# ziffy_board_v5.net
KiCad netlist of a schematic drawn in EAGLE
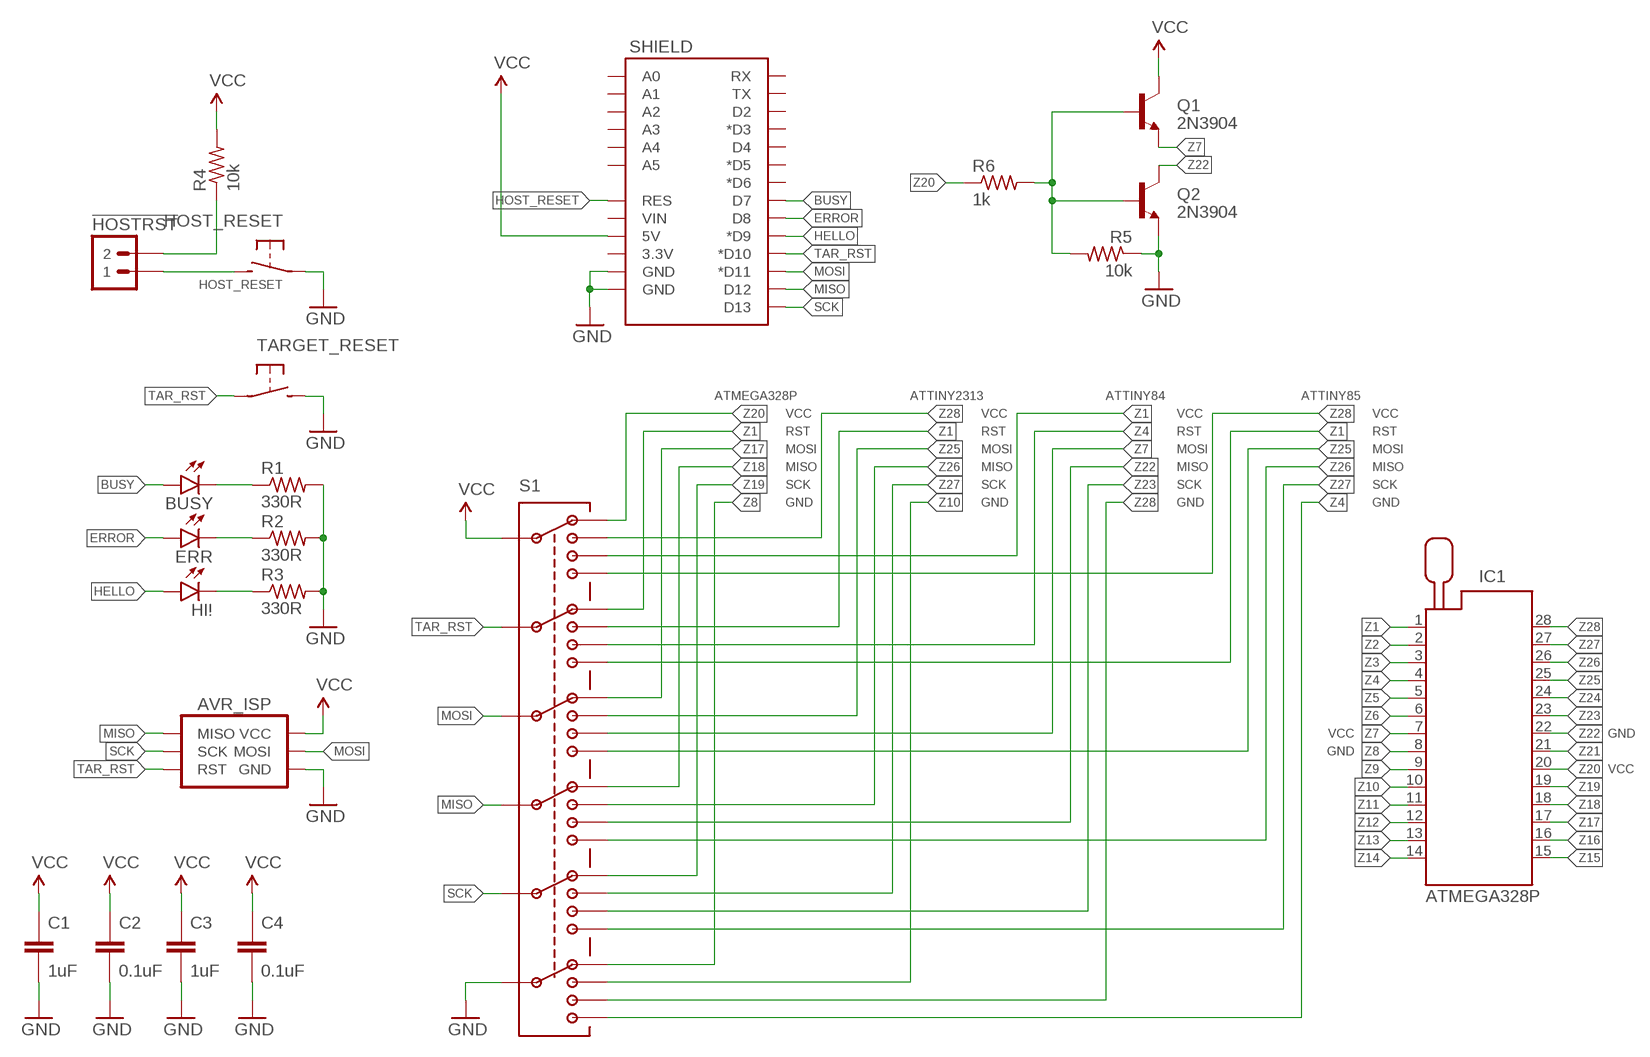
[diagram p0: schematic, sheet 1]

(export (version "E")
  (design (tool "Eeschema 10.0.6"))
  (components
    (comp (ref "!HOSTRST")
      (value "M02PTH")
      (footprint "eagle-import:1X02")
      (libsource (lib "eagle-import") (part "M02PTH"))
    )
    (comp (ref "AVR_ISP")
      (value "AVR_SPI_PRG_6PTH-SHROUD")
      (footprint "eagle-import:2X3-SHROUDED")
      (libsource (lib "eagle-import") (part "AVR_SPI_PRG_6PTH-SHROUD"))
    )
    (comp (ref "BUSY")
      (value "YELLOW")
      (footprint "eagle-import:LED3MM")
      (libsource (lib "eagle-import") (part "LED3MM"))
    )
    (comp (ref "C1")
      (value "1uF")
      (footprint "eagle-import:C025-024X044")
      (libsource (lib "eagle-import") (part "CAPACITOR-CERAMIC025-024X044"))
    )
    (comp (ref "C2")
      (value "0.1uF")
      (footprint "eagle-import:C025-024X044")
      (libsource (lib "eagle-import") (part "CAPACITOR-CERAMIC025-024X044"))
    )
    (comp (ref "C3")
      (value "1uF")
      (footprint "eagle-import:C025-024X044")
      (libsource (lib "eagle-import") (part "CAPACITOR-CERAMIC025-024X044"))
    )
    (comp (ref "C4")
      (value "0.1uF")
      (footprint "eagle-import:C025-024X044")
      (libsource (lib "eagle-import") (part "CAPACITOR-CERAMIC025-024X044"))
    )
    (comp (ref "ERR")
      (value "RED")
      (footprint "eagle-import:LED3MM")
      (libsource (lib "eagle-import") (part "LED3MM"))
    )
    (comp (ref "HI!")
      (value "GREEN")
      (footprint "eagle-import:LED3MM")
      (libsource (lib "eagle-import") (part "LED3MM"))
    )
    (comp (ref "HOST_RESET")
      (value "SPST-NO-TACT6MM-PTH-SMALL-PADS")
      (footprint "eagle-import:DTS-6-SMALL-PADS")
      (libsource (lib "eagle-import") (part "SPST-NO-TACT6MM-PTH-SMALL-PADS"))
    )
    (comp (ref "IC1")
      (value "ATMEGA328P")
      (footprint "eagle-import:ZIF28")
      (libsource (lib "eagle-import") (part "ZIF28"))
    )
    (comp (ref "Q1")
      (value "2N3904")
      (footprint "eagle-import:TO-92-AMMO")
      (libsource (lib "eagle-import") (part "TRANSISTOR_NPNTO-92-AMMO-EBC"))
    )
    (comp (ref "Q2")
      (value "2N3904")
      (footprint "eagle-import:TO-92-AMMO")
      (libsource (lib "eagle-import") (part "TRANSISTOR_NPNTO-92-AMMO-EBC"))
    )
    (comp (ref "R1")
      (value "330R")
      (footprint "eagle-import:RESISTOR-AXIAL-PTH-6.35MM")
      (libsource (lib "eagle-import") (part "RESISTORPTH-AXIAL-6.35MM"))
    )
    (comp (ref "R2")
      (value "330R")
      (footprint "eagle-import:RESISTOR-AXIAL-PTH-6.35MM")
      (libsource (lib "eagle-import") (part "RESISTORPTH-AXIAL-6.35MM"))
    )
    (comp (ref "R3")
      (value "330R")
      (footprint "eagle-import:RESISTOR-AXIAL-PTH-6.35MM")
      (libsource (lib "eagle-import") (part "RESISTORPTH-AXIAL-6.35MM"))
    )
    (comp (ref "R4")
      (value "10k")
      (footprint "eagle-import:RESISTOR-AXIAL-PTH-6.35MM")
      (libsource (lib "eagle-import") (part "RESISTORPTH-AXIAL-6.35MM"))
    )
    (comp (ref "R5")
      (value "10k")
      (footprint "eagle-import:RESISTOR-AXIAL-PTH-6.35MM")
      (libsource (lib "eagle-import") (part "RESISTORPTH-AXIAL-6.35MM"))
    )
    (comp (ref "R6")
      (value "1k")
      (footprint "eagle-import:RESISTOR-AXIAL-PTH-6.35MM")
      (libsource (lib "eagle-import") (part "RESISTORPTH-AXIAL-6.35MM"))
    )
    (comp (ref "S1")
      (value "SWITCH-6P4TASDFADSFSD")
      (footprint "eagle-import:SWITCH-6P4T-2MMPTH")
      (libsource (lib "eagle-import") (part "SWITCH-6P4TASDFADSFSD"))
    )
    (comp (ref "SHIELD")
      (value "ARDUINO_SHIELD_SMALLER")
      (footprint "eagle-import:ARDUINO_SHIELD_NOOUTLINE_INSIDE_SMALLER")
      (libsource (lib "eagle-import") (part "ARDUINO_SHIELD_SMALLER"))
    )
    (comp (ref "TARGET_RESET")
      (value "SPST-NO-TACT6MM-PTH-SMALL-PADS")
      (footprint "eagle-import:DTS-6-SMALL-PADS")
      (libsource (lib "eagle-import") (part "SPST-NO-TACT6MM-PTH-SMALL-PADS"))
    )
  )
  (nets
    (net (code "1") (name "BUSY") (class "Default")
      (node (ref "BUSY") (pin "A") (pinfunction "A_A") (pintype "passive"))
      (node (ref "SHIELD") (pin "D7") (pinfunction "D7_D7") (pintype "bidirectional"))
    )
    (net (code "2") (name "ERROR") (class "Default")
      (node (ref "ERR") (pin "A") (pinfunction "A_A") (pintype "passive"))
      (node (ref "SHIELD") (pin "D8") (pinfunction "D8_D8") (pintype "bidirectional"))
    )
    (net (code "3") (name "GND") (class "Default")
      (node (ref "AVR_ISP") (pin "6") (pinfunction "GND_6") (pintype "passive"))
      (node (ref "C1") (pin "2") (pinfunction "2_2") (pintype "passive"))
      (node (ref "C2") (pin "2") (pinfunction "2_2") (pintype "passive"))
      (node (ref "C3") (pin "2") (pinfunction "2_2") (pintype "passive"))
      (node (ref "C4") (pin "2") (pinfunction "2_2") (pintype "passive"))
      (node (ref "HOST_RESET") (pin "1") (pinfunction "1_1") (pintype "passive"))
      (node (ref "HOST_RESET") (pin "2") (pinfunction "1_2") (pintype "passive"))
      (node (ref "Q2") (pin "1") (pinfunction "E_1") (pintype "passive"))
      (node (ref "R1") (pin "P$2") (pinfunction "2_P$2") (pintype "passive"))
      (node (ref "R2") (pin "P$2") (pinfunction "2_P$2") (pintype "passive"))
      (node (ref "R3") (pin "P$2") (pinfunction "2_P$2") (pintype "passive"))
      (node (ref "R5") (pin "P$1") (pinfunction "1_P$1") (pintype "passive"))
      (node (ref "S1") (pin "P28") (pinfunction "28_P28") (pintype "bidirectional"))
      (node (ref "SHIELD") (pin "GND@0") (pinfunction "GND_GND@0") (pintype "bidirectional"))
      (node (ref "SHIELD") (pin "GND@1") (pinfunction "GND_GND@1") (pintype "bidirectional"))
      (node (ref "TARGET_RESET") (pin "3") (pinfunction "2_3") (pintype "passive"))
      (node (ref "TARGET_RESET") (pin "4") (pinfunction "2_4") (pintype "passive"))
    )
    (net (code "4") (name "HELLO") (class "Default")
      (node (ref "HI!") (pin "A") (pinfunction "A_A") (pintype "passive"))
      (node (ref "SHIELD") (pin "D9") (pinfunction "*D9_D9") (pintype "bidirectional"))
    )
    (net (code "5") (name "HOST_RESET") (class "Default")
      (node (ref "!HOSTRST") (pin "1") (pinfunction "1_1") (pintype "passive"))
      (node (ref "HOST_RESET") (pin "3") (pinfunction "2_3") (pintype "passive"))
      (node (ref "HOST_RESET") (pin "4") (pinfunction "2_4") (pintype "passive"))
      (node (ref "SHIELD") (pin "RES") (pinfunction "RES_RES") (pintype "bidirectional"))
    )
    (net (code "6") (name "MISO") (class "Default")
      (node (ref "AVR_ISP") (pin "1") (pinfunction "MISO_1") (pintype "passive"))
      (node (ref "S1") (pin "P18") (pinfunction "18_P18") (pintype "bidirectional"))
      (node (ref "SHIELD") (pin "D12") (pinfunction "D12_D12") (pintype "bidirectional"))
    )
    (net (code "7") (name "MOSI") (class "Default")
      (node (ref "AVR_ISP") (pin "4") (pinfunction "MOSI_4") (pintype "passive"))
      (node (ref "S1") (pin "P13") (pinfunction "13_P13") (pintype "bidirectional"))
      (node (ref "SHIELD") (pin "D11") (pinfunction "*D11_D11") (pintype "bidirectional"))
    )
    (net (code "8") (name "Net-(BUSY-C)") (class "Default")
      (node (ref "BUSY") (pin "K") (pinfunction "C_K") (pintype "passive"))
      (node (ref "R1") (pin "P$1") (pinfunction "1_P$1") (pintype "passive"))
    )
    (net (code "9") (name "Net-(ERR-C)") (class "Default")
      (node (ref "ERR") (pin "K") (pinfunction "C_K") (pintype "passive"))
      (node (ref "R2") (pin "P$1") (pinfunction "1_P$1") (pintype "passive"))
    )
    (net (code "10") (name "Net-(HI!-C)") (class "Default")
      (node (ref "HI!") (pin "K") (pinfunction "C_K") (pintype "passive"))
      (node (ref "R3") (pin "P$1") (pinfunction "1_P$1") (pintype "passive"))
    )
    (net (code "11") (name "Net-(Q1-B)") (class "Default")
      (node (ref "Q1") (pin "2") (pinfunction "B_2") (pintype "passive"))
      (node (ref "Q2") (pin "2") (pinfunction "B_2") (pintype "passive"))
      (node (ref "R5") (pin "P$2") (pinfunction "2_P$2") (pintype "passive"))
      (node (ref "R6") (pin "P$2") (pinfunction "2_P$2") (pintype "passive"))
    )
    (net (code "12") (name "Net-(R4-1)") (class "Default")
      (node (ref "!HOSTRST") (pin "2") (pinfunction "2_2") (pintype "passive"))
      (node (ref "R4") (pin "P$1") (pinfunction "1_P$1") (pintype "passive"))
    )
    (net (code "13") (name "SCK") (class "Default")
      (node (ref "AVR_ISP") (pin "3") (pinfunction "SCK_3") (pintype "passive"))
      (node (ref "S1") (pin "P23") (pinfunction "23_P23") (pintype "bidirectional"))
      (node (ref "SHIELD") (pin "D13") (pinfunction "D13_D13") (pintype "bidirectional"))
    )
    (net (code "14") (name "TAR_RST") (class "Default")
      (node (ref "AVR_ISP") (pin "5") (pinfunction "RST_5") (pintype "passive"))
      (node (ref "S1") (pin "P8") (pinfunction "8_P8") (pintype "bidirectional"))
      (node (ref "SHIELD") (pin "D10") (pinfunction "*D10_D10") (pintype "bidirectional"))
      (node (ref "TARGET_RESET") (pin "1") (pinfunction "1_1") (pintype "passive"))
      (node (ref "TARGET_RESET") (pin "2") (pinfunction "1_2") (pintype "passive"))
    )
    (net (code "15") (name "VCC") (class "Default")
      (node (ref "AVR_ISP") (pin "2") (pinfunction "VCC_2") (pintype "passive"))
      (node (ref "C1") (pin "1") (pinfunction "1_1") (pintype "passive"))
      (node (ref "C2") (pin "1") (pinfunction "1_1") (pintype "passive"))
      (node (ref "C3") (pin "1") (pinfunction "1_1") (pintype "passive"))
      (node (ref "C4") (pin "1") (pinfunction "1_1") (pintype "passive"))
      (node (ref "Q1") (pin "3") (pinfunction "C_3") (pintype "passive"))
      (node (ref "R4") (pin "P$2") (pinfunction "2_P$2") (pintype "passive"))
      (node (ref "S1") (pin "P3") (pinfunction "3_P3") (pintype "bidirectional"))
      (node (ref "SHIELD") (pin "5V") (pinfunction "5V_5V") (pintype "bidirectional"))
    )
    (net (code "16") (name "Z1") (class "Default")
      (node (ref "IC1") (pin "1") (pinfunction "1_1") (pintype "passive"))
      (node (ref "S1") (pin "P10") (pinfunction "10_P10") (pintype "bidirectional"))
      (node (ref "S1") (pin "P4") (pinfunction "4_P4") (pintype "bidirectional"))
      (node (ref "S1") (pin "P6") (pinfunction "6_P6") (pintype "bidirectional"))
      (node (ref "S1") (pin "P7") (pinfunction "7_P7") (pintype "bidirectional"))
    )
    (net (code "17") (name "Z2") (class "Default")
      (node (ref "IC1") (pin "2") (pinfunction "2_2") (pintype "passive"))
    )
    (net (code "18") (name "Z3") (class "Default")
      (node (ref "IC1") (pin "3") (pinfunction "3_3") (pintype "passive"))
    )
    (net (code "19") (name "Z4") (class "Default")
      (node (ref "IC1") (pin "4") (pinfunction "4_4") (pintype "passive"))
      (node (ref "S1") (pin "P30") (pinfunction "30_P30") (pintype "bidirectional"))
      (node (ref "S1") (pin "P9") (pinfunction "9_P9") (pintype "bidirectional"))
    )
    (net (code "20") (name "Z5") (class "Default")
      (node (ref "IC1") (pin "5") (pinfunction "5_5") (pintype "passive"))
    )
    (net (code "21") (name "Z6") (class "Default")
      (node (ref "IC1") (pin "6") (pinfunction "6_6") (pintype "passive"))
    )
    (net (code "22") (name "Z7") (class "Default")
      (node (ref "IC1") (pin "7") (pinfunction "7_7") (pintype "passive"))
      (node (ref "Q1") (pin "1") (pinfunction "E_1") (pintype "passive"))
      (node (ref "S1") (pin "P14") (pinfunction "14_P14") (pintype "bidirectional"))
    )
    (net (code "23") (name "Z8") (class "Default")
      (node (ref "IC1") (pin "8") (pinfunction "8_8") (pintype "passive"))
      (node (ref "S1") (pin "P26") (pinfunction "26_P26") (pintype "bidirectional"))
    )
    (net (code "24") (name "Z9") (class "Default")
      (node (ref "IC1") (pin "9") (pinfunction "9_9") (pintype "passive"))
    )
    (net (code "25") (name "Z10") (class "Default")
      (node (ref "IC1") (pin "10") (pinfunction "10_10") (pintype "passive"))
      (node (ref "S1") (pin "P27") (pinfunction "27_P27") (pintype "bidirectional"))
    )
    (net (code "26") (name "Z11") (class "Default")
      (node (ref "IC1") (pin "11") (pinfunction "11_11") (pintype "passive"))
    )
    (net (code "27") (name "Z12") (class "Default")
      (node (ref "IC1") (pin "12") (pinfunction "12_12") (pintype "passive"))
    )
    (net (code "28") (name "Z13") (class "Default")
      (node (ref "IC1") (pin "13") (pinfunction "13_13") (pintype "passive"))
    )
    (net (code "29") (name "Z14") (class "Default")
      (node (ref "IC1") (pin "14") (pinfunction "14_14") (pintype "passive"))
    )
    (net (code "30") (name "Z15") (class "Default")
      (node (ref "IC1") (pin "15") (pinfunction "15_15") (pintype "passive"))
    )
    (net (code "31") (name "Z16") (class "Default")
      (node (ref "IC1") (pin "16") (pinfunction "16_16") (pintype "passive"))
    )
    (net (code "32") (name "Z17") (class "Default")
      (node (ref "IC1") (pin "17") (pinfunction "17_17") (pintype "passive"))
      (node (ref "S1") (pin "P11") (pinfunction "11_P11") (pintype "bidirectional"))
    )
    (net (code "33") (name "Z18") (class "Default")
      (node (ref "IC1") (pin "18") (pinfunction "18_18") (pintype "passive"))
      (node (ref "S1") (pin "P16") (pinfunction "16_P16") (pintype "bidirectional"))
    )
    (net (code "34") (name "Z19") (class "Default")
      (node (ref "IC1") (pin "19") (pinfunction "19_19") (pintype "passive"))
      (node (ref "S1") (pin "P21") (pinfunction "21_P21") (pintype "bidirectional"))
    )
    (net (code "35") (name "Z20") (class "Default")
      (node (ref "IC1") (pin "20") (pinfunction "20_20") (pintype "passive"))
      (node (ref "R6") (pin "P$1") (pinfunction "1_P$1") (pintype "passive"))
      (node (ref "S1") (pin "P1") (pinfunction "1_P1") (pintype "bidirectional"))
    )
    (net (code "36") (name "Z21") (class "Default")
      (node (ref "IC1") (pin "21") (pinfunction "21_21") (pintype "passive"))
    )
    (net (code "37") (name "Z22") (class "Default")
      (node (ref "IC1") (pin "22") (pinfunction "22_22") (pintype "passive"))
      (node (ref "Q2") (pin "3") (pinfunction "C_3") (pintype "passive"))
      (node (ref "S1") (pin "P19") (pinfunction "19_P19") (pintype "bidirectional"))
    )
    (net (code "38") (name "Z23") (class "Default")
      (node (ref "IC1") (pin "23") (pinfunction "23_23") (pintype "passive"))
      (node (ref "S1") (pin "P24") (pinfunction "24_P24") (pintype "bidirectional"))
    )
    (net (code "39") (name "Z24") (class "Default")
      (node (ref "IC1") (pin "24") (pinfunction "24_24") (pintype "passive"))
    )
    (net (code "40") (name "Z25") (class "Default")
      (node (ref "IC1") (pin "25") (pinfunction "25_25") (pintype "passive"))
      (node (ref "S1") (pin "P12") (pinfunction "12_P12") (pintype "bidirectional"))
      (node (ref "S1") (pin "P15") (pinfunction "15_P15") (pintype "bidirectional"))
    )
    (net (code "41") (name "Z26") (class "Default")
      (node (ref "IC1") (pin "26") (pinfunction "26_26") (pintype "passive"))
      (node (ref "S1") (pin "P17") (pinfunction "17_P17") (pintype "bidirectional"))
      (node (ref "S1") (pin "P20") (pinfunction "20_P20") (pintype "bidirectional"))
    )
    (net (code "42") (name "Z27") (class "Default")
      (node (ref "IC1") (pin "27") (pinfunction "27_27") (pintype "passive"))
      (node (ref "S1") (pin "P22") (pinfunction "22_P22") (pintype "bidirectional"))
      (node (ref "S1") (pin "P25") (pinfunction "25_P25") (pintype "bidirectional"))
    )
    (net (code "43") (name "Z28") (class "Default")
      (node (ref "IC1") (pin "28") (pinfunction "28_28") (pintype "passive"))
      (node (ref "S1") (pin "P2") (pinfunction "2_P2") (pintype "bidirectional"))
      (node (ref "S1") (pin "P29") (pinfunction "29_P29") (pintype "bidirectional"))
      (node (ref "S1") (pin "P5") (pinfunction "5_P5") (pintype "bidirectional"))
    )
    (net (code "44") (name "unconnected-(SHIELD-*D3-PadD3)") (class "Default")
      (node (ref "SHIELD") (pin "D3") (pinfunction "*D3_D3") (pintype "bidirectional"))
    )
    (net (code "45") (name "unconnected-(SHIELD-*D5-PadD5)") (class "Default")
      (node (ref "SHIELD") (pin "D5") (pinfunction "*D5_D5") (pintype "bidirectional"))
    )
    (net (code "46") (name "unconnected-(SHIELD-*D6-PadD6)") (class "Default")
      (node (ref "SHIELD") (pin "D6") (pinfunction "*D6_D6") (pintype "bidirectional"))
    )
    (net (code "47") (name "unconnected-(SHIELD-Pad3.3V)") (class "Default")
      (node (ref "SHIELD") (pin "3.3V") (pinfunction "3.3V_3.3V") (pintype "bidirectional"))
    )
    (net (code "48") (name "unconnected-(SHIELD-PadA0)") (class "Default")
      (node (ref "SHIELD") (pin "A0") (pinfunction "A0_A0") (pintype "bidirectional"))
    )
    (net (code "49") (name "unconnected-(SHIELD-PadA1)") (class "Default")
      (node (ref "SHIELD") (pin "A1") (pinfunction "A1_A1") (pintype "bidirectional"))
    )
    (net (code "50") (name "unconnected-(SHIELD-PadA2)") (class "Default")
      (node (ref "SHIELD") (pin "A2") (pinfunction "A2_A2") (pintype "bidirectional"))
    )
    (net (code "51") (name "unconnected-(SHIELD-PadA3)") (class "Default")
      (node (ref "SHIELD") (pin "A3") (pinfunction "A3_A3") (pintype "bidirectional"))
    )
    (net (code "52") (name "unconnected-(SHIELD-PadA4)") (class "Default")
      (node (ref "SHIELD") (pin "A4") (pinfunction "A4_A4") (pintype "bidirectional"))
    )
    (net (code "53") (name "unconnected-(SHIELD-PadA5)") (class "Default")
      (node (ref "SHIELD") (pin "A5") (pinfunction "A5_A5") (pintype "bidirectional"))
    )
    (net (code "54") (name "unconnected-(SHIELD-PadD2)") (class "Default")
      (node (ref "SHIELD") (pin "D2") (pinfunction "D2_D2") (pintype "bidirectional"))
    )
    (net (code "55") (name "unconnected-(SHIELD-PadD4)") (class "Default")
      (node (ref "SHIELD") (pin "D4") (pinfunction "D4_D4") (pintype "bidirectional"))
    )
    (net (code "56") (name "unconnected-(SHIELD-PadRX)") (class "Default")
      (node (ref "SHIELD") (pin "RX") (pinfunction "RX_RX") (pintype "bidirectional"))
    )
    (net (code "57") (name "unconnected-(SHIELD-PadTX)") (class "Default")
      (node (ref "SHIELD") (pin "TX") (pinfunction "TX_TX") (pintype "bidirectional"))
    )
    (net (code "58") (name "unconnected-(SHIELD-PadVIN)") (class "Default")
      (node (ref "SHIELD") (pin "VIN") (pinfunction "VIN_VIN") (pintype "bidirectional"))
    )
  )
)
